# led-flex-board.net
KiCad netlist of a schematic drawn in EAGLE
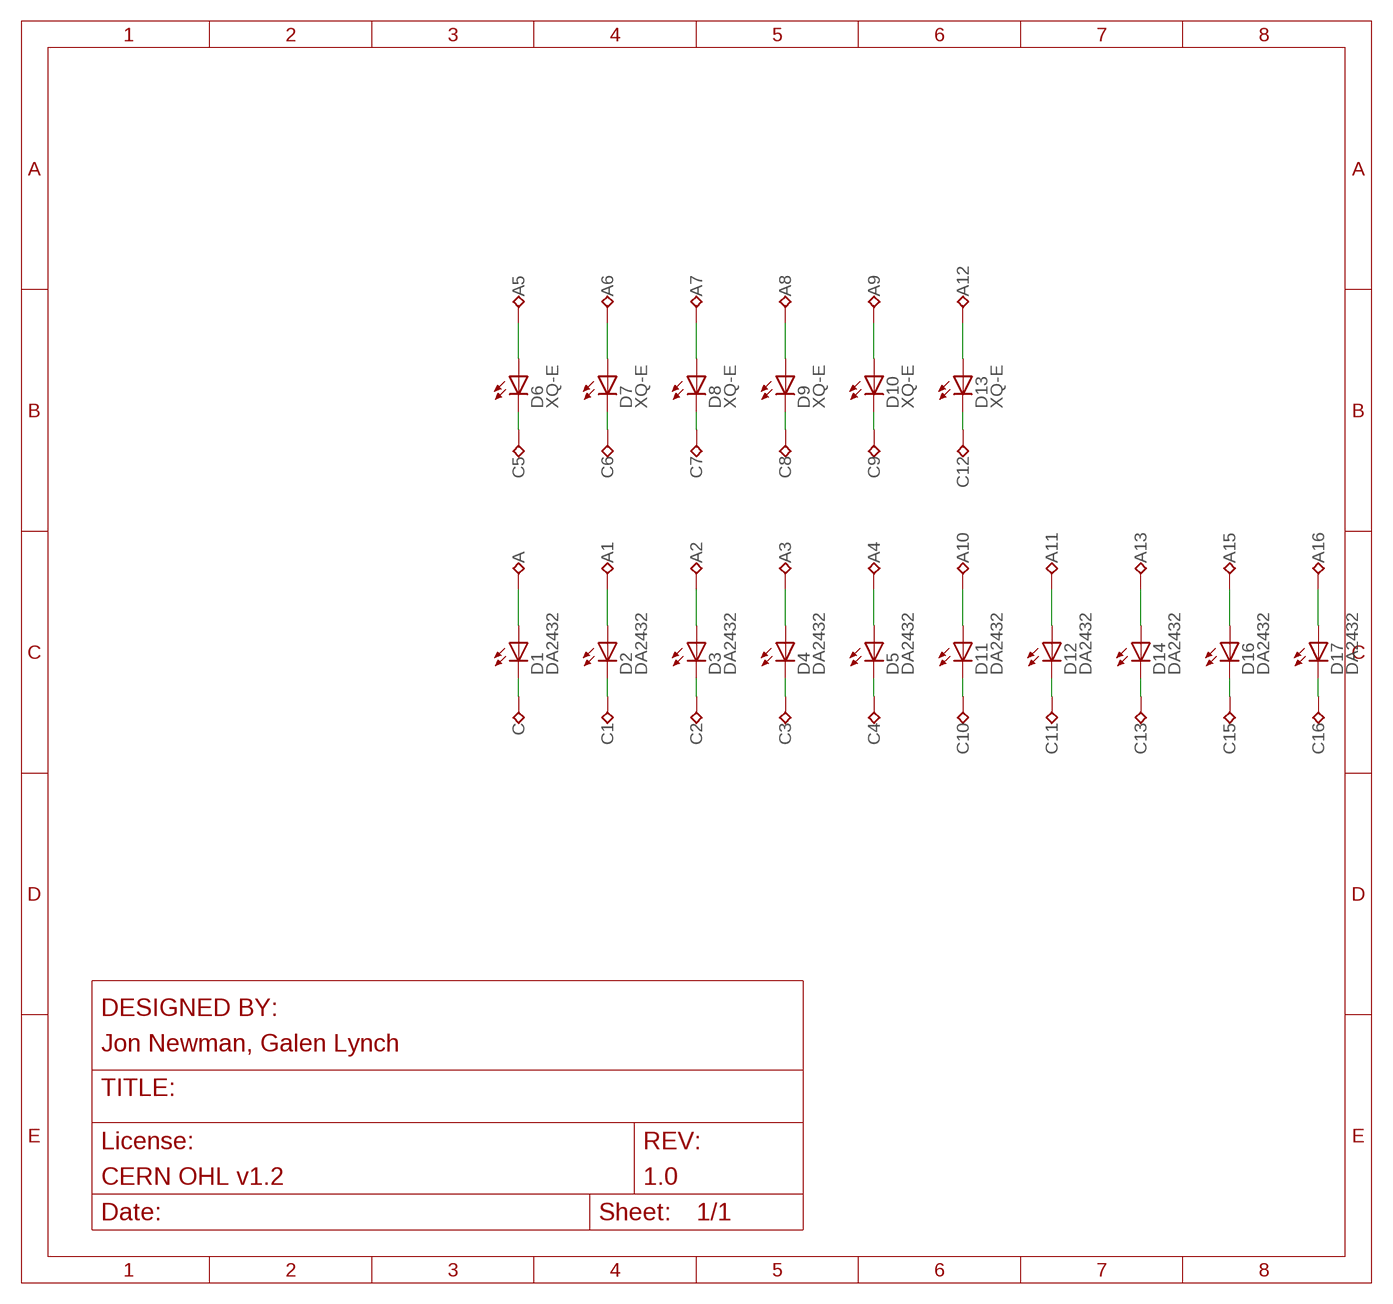
[diagram p0: schematic, sheet 1]

(export (version "E")
  (design (tool "Eeschema 10.0.6"))
  (components
    (comp (ref "A")
      (value "TP_S0.6X1.5MM")
      (footprint "eagle-import:S0.6X1.5MM")
      (libsource (lib "eagle-import") (part "TP_S0.6X1.5MM"))
    )
    (comp (ref "A1")
      (value "TP_S0.6X1.5MM")
      (footprint "eagle-import:S0.6X1.5MM")
      (libsource (lib "eagle-import") (part "TP_S0.6X1.5MM"))
    )
    (comp (ref "A2")
      (value "TP_S0.6X1.5MM")
      (footprint "eagle-import:S0.6X1.5MM")
      (libsource (lib "eagle-import") (part "TP_S0.6X1.5MM"))
    )
    (comp (ref "A3")
      (value "TP_S0.6X1.5MM")
      (footprint "eagle-import:S0.6X1.5MM")
      (libsource (lib "eagle-import") (part "TP_S0.6X1.5MM"))
    )
    (comp (ref "A4")
      (value "TP_S0.6X1.5MM")
      (footprint "eagle-import:S0.6X1.5MM")
      (libsource (lib "eagle-import") (part "TP_S0.6X1.5MM"))
    )
    (comp (ref "A5")
      (value "TP_S0.6X1.5MM")
      (footprint "eagle-import:S0.6X1.5MM")
      (libsource (lib "eagle-import") (part "TP_S0.6X1.5MM"))
    )
    (comp (ref "A6")
      (value "TP_S0.6X1.5MM")
      (footprint "eagle-import:S0.6X1.5MM")
      (libsource (lib "eagle-import") (part "TP_S0.6X1.5MM"))
    )
    (comp (ref "A7")
      (value "TP_S0.6X1.5MM")
      (footprint "eagle-import:S0.6X1.5MM")
      (libsource (lib "eagle-import") (part "TP_S0.6X1.5MM"))
    )
    (comp (ref "A8")
      (value "TP_S0.6X1.5MM")
      (footprint "eagle-import:S0.6X1.5MM")
      (libsource (lib "eagle-import") (part "TP_S0.6X1.5MM"))
    )
    (comp (ref "A9")
      (value "TP_S0.6X1.5MM")
      (footprint "eagle-import:S0.6X1.5MM")
      (libsource (lib "eagle-import") (part "TP_S0.6X1.5MM"))
    )
    (comp (ref "A10")
      (value "TP_S0.6X1.5MM")
      (footprint "eagle-import:S0.6X1.5MM")
      (libsource (lib "eagle-import") (part "TP_S0.6X1.5MM"))
    )
    (comp (ref "A11")
      (value "TP_S0.6X1.5MM")
      (footprint "eagle-import:S0.6X1.5MM")
      (libsource (lib "eagle-import") (part "TP_S0.6X1.5MM"))
    )
    (comp (ref "A12")
      (value "TP_S0.6X1.5MM")
      (footprint "eagle-import:S0.6X1.5MM")
      (libsource (lib "eagle-import") (part "TP_S0.6X1.5MM"))
    )
    (comp (ref "A13")
      (value "TP_S0.6X1.5MM")
      (footprint "eagle-import:S0.6X1.5MM")
      (libsource (lib "eagle-import") (part "TP_S0.6X1.5MM"))
    )
    (comp (ref "A15")
      (value "TP_S0.6X1.5MM")
      (footprint "eagle-import:S0.6X1.5MM")
      (libsource (lib "eagle-import") (part "TP_S0.6X1.5MM"))
    )
    (comp (ref "A16")
      (value "TP_S0.6X1.5MM")
      (footprint "eagle-import:S0.6X1.5MM")
      (libsource (lib "eagle-import") (part "TP_S0.6X1.5MM"))
    )
    (comp (ref "C")
      (value "TP_S0.6X1.5MM")
      (footprint "eagle-import:S0.6X1.5MM")
      (libsource (lib "eagle-import") (part "TP_S0.6X1.5MM"))
    )
    (comp (ref "C1")
      (value "TP_S0.6X1.5MM")
      (footprint "eagle-import:S0.6X1.5MM")
      (libsource (lib "eagle-import") (part "TP_S0.6X1.5MM"))
    )
    (comp (ref "C2")
      (value "TP_S0.6X1.5MM")
      (footprint "eagle-import:S0.6X1.5MM")
      (libsource (lib "eagle-import") (part "TP_S0.6X1.5MM"))
    )
    (comp (ref "C3")
      (value "TP_S0.6X1.5MM")
      (footprint "eagle-import:S0.6X1.5MM")
      (libsource (lib "eagle-import") (part "TP_S0.6X1.5MM"))
    )
    (comp (ref "C4")
      (value "TP_S0.6X1.5MM")
      (footprint "eagle-import:S0.6X1.5MM")
      (libsource (lib "eagle-import") (part "TP_S0.6X1.5MM"))
    )
    (comp (ref "C5")
      (value "TP_S0.6X1.5MM")
      (footprint "eagle-import:S0.6X1.5MM")
      (libsource (lib "eagle-import") (part "TP_S0.6X1.5MM"))
    )
    (comp (ref "C6")
      (value "TP_S0.6X1.5MM")
      (footprint "eagle-import:S0.6X1.5MM")
      (libsource (lib "eagle-import") (part "TP_S0.6X1.5MM"))
    )
    (comp (ref "C7")
      (value "TP_S0.6X1.5MM")
      (footprint "eagle-import:S0.6X1.5MM")
      (libsource (lib "eagle-import") (part "TP_S0.6X1.5MM"))
    )
    (comp (ref "C8")
      (value "TP_S0.6X1.5MM")
      (footprint "eagle-import:S0.6X1.5MM")
      (libsource (lib "eagle-import") (part "TP_S0.6X1.5MM"))
    )
    (comp (ref "C9")
      (value "TP_S0.6X1.5MM")
      (footprint "eagle-import:S0.6X1.5MM")
      (libsource (lib "eagle-import") (part "TP_S0.6X1.5MM"))
    )
    (comp (ref "C10")
      (value "TP_S0.6X1.5MM")
      (footprint "eagle-import:S0.6X1.5MM")
      (libsource (lib "eagle-import") (part "TP_S0.6X1.5MM"))
    )
    (comp (ref "C11")
      (value "TP_S0.6X1.5MM")
      (footprint "eagle-import:S0.6X1.5MM")
      (libsource (lib "eagle-import") (part "TP_S0.6X1.5MM"))
    )
    (comp (ref "C12")
      (value "TP_S0.6X1.5MM")
      (footprint "eagle-import:S0.6X1.5MM")
      (libsource (lib "eagle-import") (part "TP_S0.6X1.5MM"))
    )
    (comp (ref "C13")
      (value "TP_S0.6X1.5MM")
      (footprint "eagle-import:S0.6X1.5MM")
      (libsource (lib "eagle-import") (part "TP_S0.6X1.5MM"))
    )
    (comp (ref "C15")
      (value "TP_S0.6X1.5MM")
      (footprint "eagle-import:S0.6X1.5MM")
      (libsource (lib "eagle-import") (part "TP_S0.6X1.5MM"))
    )
    (comp (ref "C16")
      (value "TP_S0.6X1.5MM")
      (footprint "eagle-import:S0.6X1.5MM")
      (libsource (lib "eagle-import") (part "TP_S0.6X1.5MM"))
    )
    (comp (ref "D1")
      (value "DA2432")
      (footprint "eagle-import:DA2432")
      (libsource (lib "eagle-import") (part "LED_DA2432"))
    )
    (comp (ref "D2")
      (value "DA2432")
      (footprint "eagle-import:DA2432")
      (libsource (lib "eagle-import") (part "LED_DA2432"))
    )
    (comp (ref "D3")
      (value "DA2432")
      (footprint "eagle-import:DA2432")
      (libsource (lib "eagle-import") (part "LED_DA2432"))
    )
    (comp (ref "D4")
      (value "DA2432")
      (footprint "eagle-import:DA2432")
      (libsource (lib "eagle-import") (part "LED_DA2432"))
    )
    (comp (ref "D5")
      (value "DA2432")
      (footprint "eagle-import:DA2432")
      (libsource (lib "eagle-import") (part "LED_DA2432"))
    )
    (comp (ref "D6")
      (value "XQ-E")
      (footprint "eagle-import:XLAMP_1.6X1.6MM")
      (libsource (lib "eagle-import") (part "LED_XLAMP1.6X1.6MM"))
    )
    (comp (ref "D7")
      (value "XQ-E")
      (footprint "eagle-import:XLAMP_1.6X1.6MM")
      (libsource (lib "eagle-import") (part "LED_XLAMP1.6X1.6MM"))
    )
    (comp (ref "D8")
      (value "XQ-E")
      (footprint "eagle-import:XLAMP_1.6X1.6MM")
      (libsource (lib "eagle-import") (part "LED_XLAMP1.6X1.6MM"))
    )
    (comp (ref "D9")
      (value "XQ-E")
      (footprint "eagle-import:XLAMP_1.6X1.6MM")
      (libsource (lib "eagle-import") (part "LED_XLAMP1.6X1.6MM"))
    )
    (comp (ref "D10")
      (value "XQ-E")
      (footprint "eagle-import:XLAMP_1.6X1.6MM")
      (libsource (lib "eagle-import") (part "LED_XLAMP1.6X1.6MM"))
    )
    (comp (ref "D11")
      (value "DA2432")
      (footprint "eagle-import:DA2432")
      (libsource (lib "eagle-import") (part "LED_DA2432"))
    )
    (comp (ref "D12")
      (value "DA2432")
      (footprint "eagle-import:DA2432")
      (libsource (lib "eagle-import") (part "LED_DA2432"))
    )
    (comp (ref "D13")
      (value "XQ-E")
      (footprint "eagle-import:XLAMP_1.6X1.6MM")
      (libsource (lib "eagle-import") (part "LED_XLAMP1.6X1.6MM"))
    )
    (comp (ref "D14")
      (value "DA2432")
      (footprint "eagle-import:DA2432")
      (libsource (lib "eagle-import") (part "LED_DA2432"))
    )
    (comp (ref "D16")
      (value "DA2432")
      (footprint "eagle-import:DA2432")
      (libsource (lib "eagle-import") (part "LED_DA2432"))
    )
    (comp (ref "D17")
      (value "DA2432")
      (footprint "eagle-import:DA2432")
      (libsource (lib "eagle-import") (part "LED_DA2432"))
    )
  )
  (nets
    (net (code "1") (name "Net-(A-PadTP)") (class "Default")
      (node (ref "A") (pin "TP") (pinfunction "TP_TP") (pintype "bidirectional"))
      (node (ref "D1") (pin "A") (pinfunction "A_A") (pintype "passive"))
    )
    (net (code "2") (name "Net-(A1-PadTP)") (class "Default")
      (node (ref "A1") (pin "TP") (pinfunction "TP_TP") (pintype "bidirectional"))
      (node (ref "D2") (pin "A") (pinfunction "A_A") (pintype "passive"))
    )
    (net (code "3") (name "Net-(A2-PadTP)") (class "Default")
      (node (ref "A2") (pin "TP") (pinfunction "TP_TP") (pintype "bidirectional"))
      (node (ref "D3") (pin "A") (pinfunction "A_A") (pintype "passive"))
    )
    (net (code "4") (name "Net-(A3-PadTP)") (class "Default")
      (node (ref "A3") (pin "TP") (pinfunction "TP_TP") (pintype "bidirectional"))
      (node (ref "D4") (pin "A") (pinfunction "A_A") (pintype "passive"))
    )
    (net (code "5") (name "Net-(A4-PadTP)") (class "Default")
      (node (ref "A4") (pin "TP") (pinfunction "TP_TP") (pintype "bidirectional"))
      (node (ref "D5") (pin "A") (pinfunction "A_A") (pintype "passive"))
    )
    (net (code "6") (name "Net-(A5-PadTP)") (class "Default")
      (node (ref "A5") (pin "TP") (pinfunction "TP_TP") (pintype "bidirectional"))
      (node (ref "D6") (pin "A") (pinfunction "A_A") (pintype "passive"))
    )
    (net (code "7") (name "Net-(A6-PadTP)") (class "Default")
      (node (ref "A6") (pin "TP") (pinfunction "TP_TP") (pintype "bidirectional"))
      (node (ref "D7") (pin "A") (pinfunction "A_A") (pintype "passive"))
    )
    (net (code "8") (name "Net-(A7-PadTP)") (class "Default")
      (node (ref "A7") (pin "TP") (pinfunction "TP_TP") (pintype "bidirectional"))
      (node (ref "D8") (pin "A") (pinfunction "A_A") (pintype "passive"))
    )
    (net (code "9") (name "Net-(A8-PadTP)") (class "Default")
      (node (ref "A8") (pin "TP") (pinfunction "TP_TP") (pintype "bidirectional"))
      (node (ref "D9") (pin "A") (pinfunction "A_A") (pintype "passive"))
    )
    (net (code "10") (name "Net-(A9-PadTP)") (class "Default")
      (node (ref "A9") (pin "TP") (pinfunction "TP_TP") (pintype "bidirectional"))
      (node (ref "D10") (pin "A") (pinfunction "A_A") (pintype "passive"))
    )
    (net (code "11") (name "Net-(A10-PadTP)") (class "Default")
      (node (ref "A10") (pin "TP") (pinfunction "TP_TP") (pintype "bidirectional"))
      (node (ref "D11") (pin "A") (pinfunction "A_A") (pintype "passive"))
    )
    (net (code "12") (name "Net-(A11-PadTP)") (class "Default")
      (node (ref "A11") (pin "TP") (pinfunction "TP_TP") (pintype "bidirectional"))
      (node (ref "D12") (pin "A") (pinfunction "A_A") (pintype "passive"))
    )
    (net (code "13") (name "Net-(A12-PadTP)") (class "Default")
      (node (ref "A12") (pin "TP") (pinfunction "TP_TP") (pintype "bidirectional"))
      (node (ref "D13") (pin "A") (pinfunction "A_A") (pintype "passive"))
    )
    (net (code "14") (name "Net-(A13-PadTP)") (class "Default")
      (node (ref "A13") (pin "TP") (pinfunction "TP_TP") (pintype "bidirectional"))
      (node (ref "D14") (pin "A") (pinfunction "A_A") (pintype "passive"))
    )
    (net (code "15") (name "Net-(A15-PadTP)") (class "Default")
      (node (ref "A15") (pin "TP") (pinfunction "TP_TP") (pintype "bidirectional"))
      (node (ref "D16") (pin "A") (pinfunction "A_A") (pintype "passive"))
    )
    (net (code "16") (name "Net-(A16-PadTP)") (class "Default")
      (node (ref "A16") (pin "TP") (pinfunction "TP_TP") (pintype "bidirectional"))
      (node (ref "D17") (pin "A") (pinfunction "A_A") (pintype "passive"))
    )
    (net (code "17") (name "Net-(C-PadTP)") (class "Default")
      (node (ref "C") (pin "TP") (pinfunction "TP_TP") (pintype "bidirectional"))
      (node (ref "D1") (pin "C") (pinfunction "C_C") (pintype "passive"))
    )
    (net (code "18") (name "Net-(C1-PadTP)") (class "Default")
      (node (ref "C1") (pin "TP") (pinfunction "TP_TP") (pintype "bidirectional"))
      (node (ref "D2") (pin "C") (pinfunction "C_C") (pintype "passive"))
    )
    (net (code "19") (name "Net-(C2-PadTP)") (class "Default")
      (node (ref "C2") (pin "TP") (pinfunction "TP_TP") (pintype "bidirectional"))
      (node (ref "D3") (pin "C") (pinfunction "C_C") (pintype "passive"))
    )
    (net (code "20") (name "Net-(C3-PadTP)") (class "Default")
      (node (ref "C3") (pin "TP") (pinfunction "TP_TP") (pintype "bidirectional"))
      (node (ref "D4") (pin "C") (pinfunction "C_C") (pintype "passive"))
    )
    (net (code "21") (name "Net-(C4-PadTP)") (class "Default")
      (node (ref "C4") (pin "TP") (pinfunction "TP_TP") (pintype "bidirectional"))
      (node (ref "D5") (pin "C") (pinfunction "C_C") (pintype "passive"))
    )
    (net (code "22") (name "Net-(C5-PadTP)") (class "Default")
      (node (ref "C5") (pin "TP") (pinfunction "TP_TP") (pintype "bidirectional"))
      (node (ref "D6") (pin "C") (pinfunction "C_C") (pintype "passive"))
    )
    (net (code "23") (name "Net-(C6-PadTP)") (class "Default")
      (node (ref "C6") (pin "TP") (pinfunction "TP_TP") (pintype "bidirectional"))
      (node (ref "D7") (pin "C") (pinfunction "C_C") (pintype "passive"))
    )
    (net (code "24") (name "Net-(C7-PadTP)") (class "Default")
      (node (ref "C7") (pin "TP") (pinfunction "TP_TP") (pintype "bidirectional"))
      (node (ref "D8") (pin "C") (pinfunction "C_C") (pintype "passive"))
    )
    (net (code "25") (name "Net-(C8-PadTP)") (class "Default")
      (node (ref "C8") (pin "TP") (pinfunction "TP_TP") (pintype "bidirectional"))
      (node (ref "D9") (pin "C") (pinfunction "C_C") (pintype "passive"))
    )
    (net (code "26") (name "Net-(C9-PadTP)") (class "Default")
      (node (ref "C9") (pin "TP") (pinfunction "TP_TP") (pintype "bidirectional"))
      (node (ref "D10") (pin "C") (pinfunction "C_C") (pintype "passive"))
    )
    (net (code "27") (name "Net-(C10-PadTP)") (class "Default")
      (node (ref "C10") (pin "TP") (pinfunction "TP_TP") (pintype "bidirectional"))
      (node (ref "D11") (pin "C") (pinfunction "C_C") (pintype "passive"))
    )
    (net (code "28") (name "Net-(C11-PadTP)") (class "Default")
      (node (ref "C11") (pin "TP") (pinfunction "TP_TP") (pintype "bidirectional"))
      (node (ref "D12") (pin "C") (pinfunction "C_C") (pintype "passive"))
    )
    (net (code "29") (name "Net-(C12-PadTP)") (class "Default")
      (node (ref "C12") (pin "TP") (pinfunction "TP_TP") (pintype "bidirectional"))
      (node (ref "D13") (pin "C") (pinfunction "C_C") (pintype "passive"))
    )
    (net (code "30") (name "Net-(C13-PadTP)") (class "Default")
      (node (ref "C13") (pin "TP") (pinfunction "TP_TP") (pintype "bidirectional"))
      (node (ref "D14") (pin "C") (pinfunction "C_C") (pintype "passive"))
    )
    (net (code "31") (name "Net-(C15-PadTP)") (class "Default")
      (node (ref "C15") (pin "TP") (pinfunction "TP_TP") (pintype "bidirectional"))
      (node (ref "D16") (pin "C") (pinfunction "C_C") (pintype "passive"))
    )
    (net (code "32") (name "Net-(C16-PadTP)") (class "Default")
      (node (ref "C16") (pin "TP") (pinfunction "TP_TP") (pintype "bidirectional"))
      (node (ref "D17") (pin "C") (pinfunction "C_C") (pintype "passive"))
    )
  )
)
